# MCU.net
KiCad netlist of a schematic drawn in Altium Designer
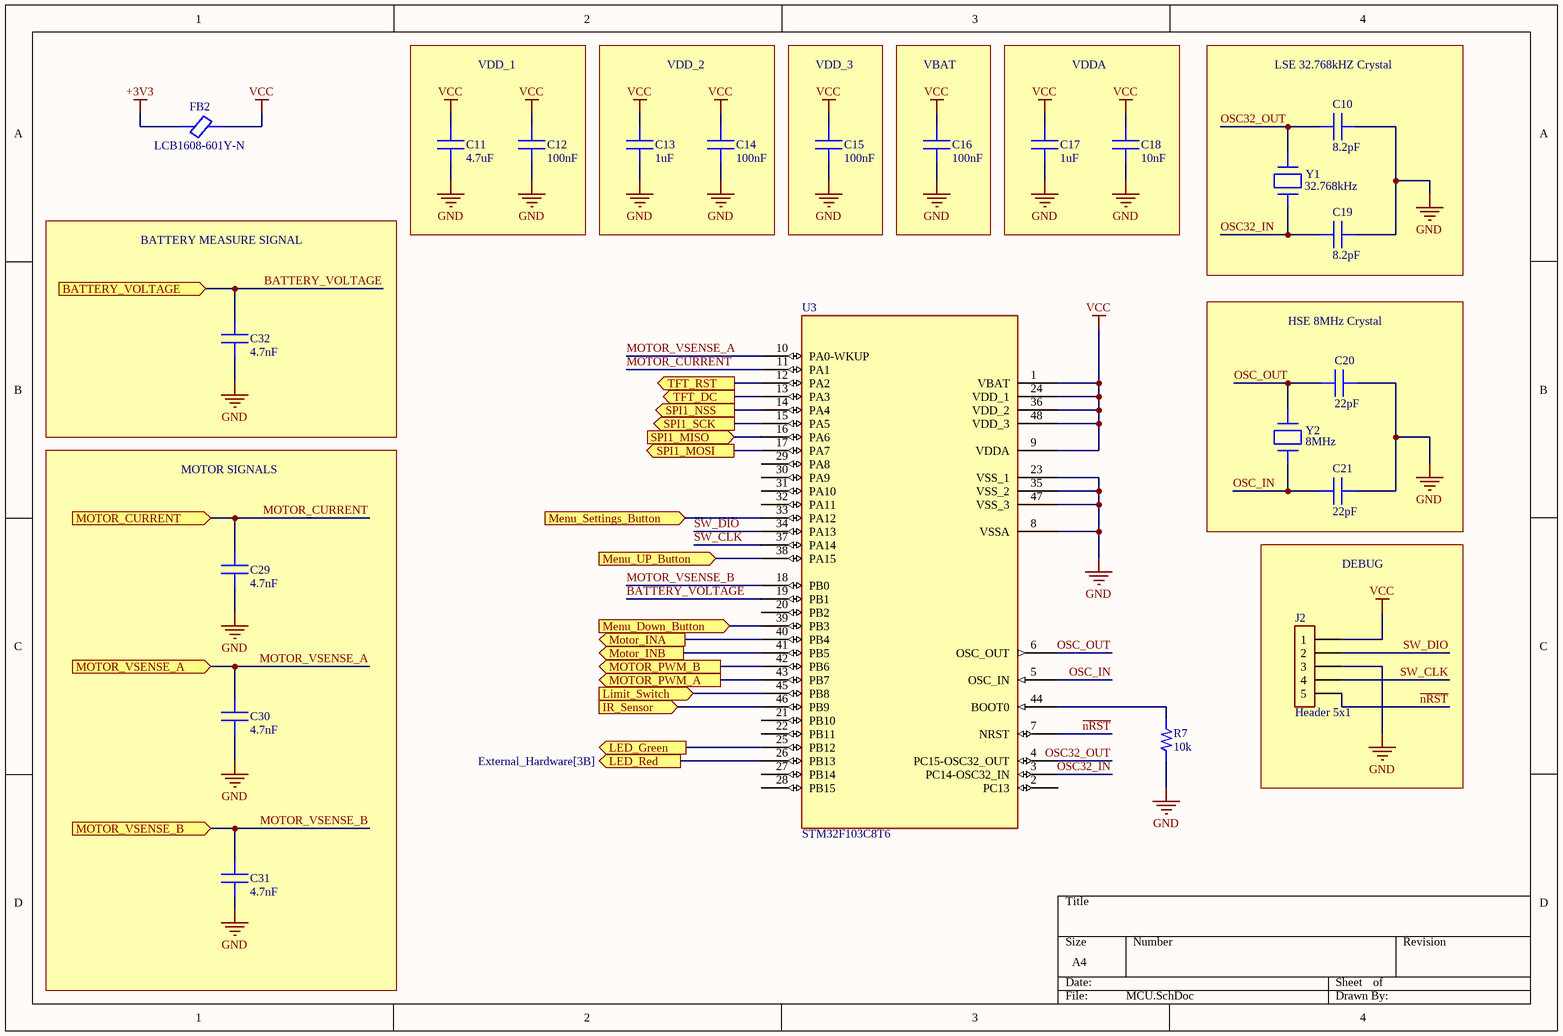
[diagram p0: MCU.SchDoc]

(export (version "E")
  (design (tool "Eeschema 10.0.6"))
  (components
    (comp (ref "C10")
      (value "8.2pF")
      (footprint "CAPC2012X145N 0805")
      (description "MLCC (2012) 0805 8.2pF 50VDC ±0.5pF C0G (NP0)")
      (fields (field (name "TOLERANCE") "±0.5 pF") (field (name "MANUFACTURER") "YAGEO"))
      (libsource (lib "Chicken_Coop_Door_Main_Board_V3") (part "CAP 0805 8.2pF CC0805DRNPO9BN8R2"))
    )
    (comp (ref "C11")
      (value "4.7uF")
      (footprint "CAPC2012X145N 0805")
      (description "MLCC (2012) 0805 4.7uF 16VDC ±10% X7R AUTOMOTIVE")
      (fields (field (name "TOLERANCE") "±10 %") (field (name "MANUFACTURER") "SAMSUNG"))
      (libsource (lib "Chicken_Coop_Door_Main_Board_V3") (part "CAP 0805 4.7uF CL21B475KOQVPNE"))
    )
    (comp (ref "C12")
      (value "100nF")
      (footprint "CAPC 0603 1608X90N")
      (description "MLCC (1608) 0603 100nF 25VDC ±10% X7R")
      (fields (field (name "TOLERANCE") "±10%") (field (name "MANUFACTURER") "YAGEO"))
      (libsource (lib "Chicken_Coop_Door_Main_Board_V3") (part "CAP 0603 100nF CC0603KPX7R8BB104"))
    )
    (comp (ref "C13")
      (value "1uF")
      (footprint "CAPC 0603 1608X90N")
      (description "MLCC (1608) 0603 1uF 16VDC ±10% X5R")
      (fields (field (name "TOLERANCE") "±10%") (field (name "MANUFACTURER") "KEMET"))
      (libsource (lib "Chicken_Coop_Door_Main_Board_V3") (part "CAP 0603 1uF C0603C105K4PACTU"))
    )
    (comp (ref "C14")
      (value "100nF")
      (footprint "CAPC 0603 1608X90N")
      (description "MLCC (1608) 0603 100nF 25VDC ±10% X7R")
      (fields (field (name "TOLERANCE") "±10%") (field (name "MANUFACTURER") "YAGEO"))
      (libsource (lib "Chicken_Coop_Door_Main_Board_V3") (part "CAP 0603 100nF CC0603KPX7R8BB104"))
    )
    (comp (ref "C15")
      (value "100nF")
      (footprint "CAPC 0603 1608X90N")
      (description "MLCC (1608) 0603 100nF 25VDC ±10% X7R")
      (fields (field (name "TOLERANCE") "±10%") (field (name "MANUFACTURER") "YAGEO"))
      (libsource (lib "Chicken_Coop_Door_Main_Board_V3") (part "CAP 0603 100nF CC0603KPX7R8BB104"))
    )
    (comp (ref "C16")
      (value "100nF")
      (footprint "CAPC 0603 1608X90N")
      (description "MLCC (1608) 0603 100nF 25VDC ±10% X7R")
      (fields (field (name "TOLERANCE") "±10%") (field (name "MANUFACTURER") "YAGEO"))
      (libsource (lib "Chicken_Coop_Door_Main_Board_V3") (part "CAP 0603 100nF CC0603KPX7R8BB104"))
    )
    (comp (ref "C17")
      (value "1uF")
      (footprint "CAPC 0603 1608X90N")
      (description "MLCC (1608) 0603 1uF 16VDC ±10% X5R")
      (fields (field (name "TOLERANCE") "±10%") (field (name "MANUFACTURER") "KEMET"))
      (libsource (lib "Chicken_Coop_Door_Main_Board_V3") (part "CAP 0603 1uF C0603C105K4PACTU"))
    )
    (comp (ref "C18")
      (value "10nF")
      (footprint "CAPC 0603 1608X90N")
      (description "MLCC (1608) 0603 10nF 25VDC ±10% X7R")
      (fields (field (name "TOLERANCE") "±10%") (field (name "MANUFACTURER") "SAMSUNG"))
      (libsource (lib "Chicken_Coop_Door_Main_Board_V3") (part "CAP 0603 10nF CL10B103KA8NNNC"))
    )
    (comp (ref "C19")
      (value "8.2pF")
      (footprint "CAPC2012X145N 0805")
      (description "MLCC (2012) 0805 8.2pF 50VDC ±0.5pF C0G (NP0)")
      (fields (field (name "TOLERANCE") "±0.5 pF") (field (name "MANUFACTURER") "YAGEO"))
      (libsource (lib "Chicken_Coop_Door_Main_Board_V3") (part "CAP 0805 8.2pF CC0805DRNPO9BN8R2"))
    )
    (comp (ref "C20")
      (value "22pF")
      (footprint "CAPC 0603 1608X90N")
      (description "MLCC (1608) 0603 22pF 50VDC ±5% C0G (NP0)")
      (fields (field (name "TOLERANCE") "±5 %") (field (name "MANUFACTURER") "YAGEO"))
      (libsource (lib "Chicken_Coop_Door_Main_Board_V3") (part "CAP 0603 22pF CC0603JRNPO9BN220"))
    )
    (comp (ref "C21")
      (value "22pF")
      (footprint "CAPC 0603 1608X90N")
      (description "MLCC (1608) 0603 22pF 50VDC ±5% C0G (NP0)")
      (fields (field (name "TOLERANCE") "±5 %") (field (name "MANUFACTURER") "YAGEO"))
      (libsource (lib "Chicken_Coop_Door_Main_Board_V3") (part "CAP 0603 22pF CC0603JRNPO9BN220"))
    )
    (comp (ref "C29")
      (value "4.7nF")
      (footprint "CAPC1608X90N 0603")
      (description "MLCC (1608) 0603 4.7nF 50VDC ±10% X7R")
      (fields (field (name "TOLERANCE") "±10 %") (field (name "MANUFACTURER") "SAMSUNG"))
      (libsource (lib "Chicken_Coop_Door_Main_Board_V3") (part "CAP 0603 4.7nF CL10B472KB8NNNC"))
    )
    (comp (ref "C30")
      (value "4.7nF")
      (footprint "CAPC1608X90N 0603")
      (description "MLCC (1608) 0603 4.7nF 50VDC ±10% X7R")
      (fields (field (name "TOLERANCE") "±10 %") (field (name "MANUFACTURER") "SAMSUNG"))
      (libsource (lib "Chicken_Coop_Door_Main_Board_V3") (part "CAP 0603 4.7nF CL10B472KB8NNNC"))
    )
    (comp (ref "C31")
      (value "4.7nF")
      (footprint "CAPC1608X90N 0603")
      (description "MLCC (1608) 0603 4.7nF 50VDC ±10% X7R")
      (fields (field (name "TOLERANCE") "±10 %") (field (name "MANUFACTURER") "SAMSUNG"))
      (libsource (lib "Chicken_Coop_Door_Main_Board_V3") (part "CAP 0603 4.7nF CL10B472KB8NNNC"))
    )
    (comp (ref "C32")
      (value "4.7nF")
      (footprint "CAPC1608X90N 0603")
      (description "MLCC (1608) 0603 4.7nF 50VDC ±10% X7R")
      (fields (field (name "TOLERANCE") "±10 %") (field (name "MANUFACTURER") "SAMSUNG"))
      (libsource (lib "Chicken_Coop_Door_Main_Board_V3") (part "CAP 0603 4.7nF CL10B472KB8NNNC"))
    )
    (comp (ref "FB2")
      (value "LCB1608-601Y-N")
      (footprint "MPZ1608S601ATA00 0603 1608X95N")
      (description "600 Ohms @ 100 MHz 1 Power Line Ferrite Bead 0603 (1608 Metric) 1A 200mOhm")
      (fields (field (name "TOLERANCE") "±25 %") (field (name "MANUFACTURER") "CORE MASTER"))
      (libsource (lib "Chicken_Coop_Door_Main_Board_V3") (part "Ferrite Bead LCB1608-601Y-N"))
    )
    (comp (ref "J2")
      (value "Header 5x1")
      (footprint "Header 5x1 FEMALE Header")
      (description "FEMALE HEADER 5PIN(1x5) 2.54mm THT V/T BAG")
      (fields (field (name "MANUFACTURER") "KLS ELECTRONIC"))
      (libsource (lib "Chicken_Coop_Door_Main_Board_V3") (part "Header 5x1 Female Header"))
    )
    (comp (ref "R7")
      (value "10k")
      (footprint "RES 0603 ROYALOHM")
      (description "RES.(1608) 0603 10K Ohms 5% 1/10W-S 100PPM")
      (fields (field (name "TOLERANCE") "±5 %") (field (name "MANUFACTURER") "ROYALOHM"))
      (libsource (lib "Chicken_Coop_Door_Main_Board_V3") (part "RES 0603 10k 0603SAJ0103T5E"))
    )
    (comp (ref "U3")
      (value "STM32F103C8T6")
      (footprint "LQFP48_STM")
      (fields (field (name "COPYRIGHT") "Copyright (C) 2025 Ultra Librarian. All rights reserved."))
      (libsource (lib "Chicken_Coop_Door_Main_Board") (part "STM32F103C8T6"))
    )
    (comp (ref "Y1")
      (value "32.768kHz")
      (footprint "XTAL_ABS07-120-32.768KHZ-T")
      (description "CRYSTAL 32.768kHz 6pF SMD")
      (fields (field (name "MANUFACTURER") "Abracon LLC"))
      (libsource (lib "Chicken_Coop_Door_Main_Board_V3") (part "CRYSTAL 32.768kHz ABS07-120-32.768KHZ-T"))
    )
    (comp (ref "Y2")
      (value "8MHz")
      (footprint "XTAL_J49SMH-A-G-G-K-8M0_JAU")
      (description "CRYSTAL 8MHz HC49SMT 16pF SMD TR RALTRON")
      (fields (field (name "MANUFACTURER") "RALTRON"))
      (libsource (lib "Chicken_Coop_Door_Main_Board_V3") (part "CRYSTAL 8MHz AS-8.000-16-SMD-TR"))
    )
  )
  (nets
    (net (code "1") (name "+3V3") (class "Default")
      (node (ref "FB2") (pin "1") (pinfunction "1_1") (pintype "passive"))
    )
    (net (code "2") (name "/BATTERY_VOLTAGE") (class "Default")
      (node (ref "C32") (pin "2") (pinfunction "2_2") (pintype "passive"))
      (node (ref "U3") (pin "19") (pinfunction "PB1_19") (pintype "bidirectional"))
    )
    (net (code "3") (name "/IR_Sensor") (class "Default")
      (node (ref "U3") (pin "46") (pinfunction "PB9_46") (pintype "bidirectional"))
    )
    (net (code "4") (name "/LED_Green") (class "Default")
      (node (ref "U3") (pin "25") (pinfunction "PB12_25") (pintype "bidirectional"))
    )
    (net (code "5") (name "/LED_Red") (class "Default")
      (node (ref "U3") (pin "26") (pinfunction "PB13_26") (pintype "bidirectional"))
    )
    (net (code "6") (name "/Limit_Switch") (class "Default")
      (node (ref "U3") (pin "45") (pinfunction "PB8_45") (pintype "bidirectional"))
    )
    (net (code "7") (name "/MOTOR_CURRENT") (class "Default")
      (node (ref "C29") (pin "2") (pinfunction "2_2") (pintype "passive"))
      (node (ref "U3") (pin "11") (pinfunction "PA1_11") (pintype "bidirectional"))
    )
    (net (code "8") (name "/MOTOR_PWM_A") (class "Default")
      (node (ref "U3") (pin "43") (pinfunction "PB7_43") (pintype "bidirectional"))
    )
    (net (code "9") (name "/MOTOR_PWM_B") (class "Default")
      (node (ref "U3") (pin "42") (pinfunction "PB6_42") (pintype "bidirectional"))
    )
    (net (code "10") (name "/MOTOR_VSENSE_A") (class "Default")
      (node (ref "C30") (pin "2") (pinfunction "2_2") (pintype "passive"))
      (node (ref "U3") (pin "10") (pinfunction "PA0-WKUP_10") (pintype "bidirectional"))
    )
    (net (code "11") (name "/MOTOR_VSENSE_B") (class "Default")
      (node (ref "C31") (pin "2") (pinfunction "2_2") (pintype "passive"))
      (node (ref "U3") (pin "18") (pinfunction "PB0_18") (pintype "bidirectional"))
    )
    (net (code "12") (name "/Menu_Down_Button") (class "Default")
      (node (ref "U3") (pin "39") (pinfunction "PB3_39") (pintype "bidirectional"))
    )
    (net (code "13") (name "/Menu_Settings_Button") (class "Default")
      (node (ref "U3") (pin "33") (pinfunction "PA12_33") (pintype "bidirectional"))
    )
    (net (code "14") (name "/Menu_UP_Button") (class "Default")
      (node (ref "U3") (pin "38") (pinfunction "PA15_38") (pintype "bidirectional"))
    )
    (net (code "15") (name "/Motor_INA") (class "Default")
      (node (ref "U3") (pin "40") (pinfunction "PB4_40") (pintype "bidirectional"))
    )
    (net (code "16") (name "/Motor_INB") (class "Default")
      (node (ref "U3") (pin "41") (pinfunction "PB5_41") (pintype "bidirectional"))
    )
    (net (code "17") (name "/OSC32_IN") (class "Default")
      (node (ref "C19") (pin "1") (pinfunction "1_1") (pintype "passive"))
      (node (ref "U3") (pin "3") (pinfunction "PC14-OSC32_IN_3") (pintype "bidirectional"))
      (node (ref "Y1") (pin "1") (pinfunction "1_1") (pintype "passive"))
    )
    (net (code "18") (name "/OSC32_OUT") (class "Default")
      (node (ref "C10") (pin "1") (pinfunction "1_1") (pintype "passive"))
      (node (ref "U3") (pin "4") (pinfunction "PC15-OSC32_OUT_4") (pintype "bidirectional"))
      (node (ref "Y1") (pin "2") (pinfunction "2_2") (pintype "passive"))
    )
    (net (code "19") (name "/OSC_IN") (class "Default")
      (node (ref "C21") (pin "1") (pinfunction "1_1") (pintype "passive"))
      (node (ref "U3") (pin "5") (pinfunction "OSC_IN_5") (pintype "input"))
      (node (ref "Y2") (pin "1") (pinfunction "1_1") (pintype "passive"))
    )
    (net (code "20") (name "/OSC_OUT") (class "Default")
      (node (ref "C20") (pin "1") (pinfunction "1_1") (pintype "passive"))
      (node (ref "U3") (pin "6") (pinfunction "OSC_OUT_6") (pintype "output"))
      (node (ref "Y2") (pin "2") (pinfunction "2_2") (pintype "passive"))
    )
    (net (code "21") (name "/SPI1_MISO") (class "Default")
      (node (ref "U3") (pin "16") (pinfunction "PA6_16") (pintype "bidirectional"))
    )
    (net (code "22") (name "/SPI1_MOSI") (class "Default")
      (node (ref "U3") (pin "17") (pinfunction "PA7_17") (pintype "bidirectional"))
    )
    (net (code "23") (name "/SPI1_NSS") (class "Default")
      (node (ref "U3") (pin "14") (pinfunction "PA4_14") (pintype "bidirectional"))
    )
    (net (code "24") (name "/SPI1_SCK") (class "Default")
      (node (ref "U3") (pin "15") (pinfunction "PA5_15") (pintype "bidirectional"))
    )
    (net (code "25") (name "/SW_CLK") (class "Default")
      (node (ref "J2") (pin "4") (pinfunction "4_4") (pintype "passive"))
      (node (ref "U3") (pin "37") (pinfunction "PA14_37") (pintype "bidirectional"))
    )
    (net (code "26") (name "/SW_DIO") (class "Default")
      (node (ref "J2") (pin "2") (pinfunction "2_2") (pintype "passive"))
      (node (ref "U3") (pin "34") (pinfunction "PA13_34") (pintype "bidirectional"))
    )
    (net (code "27") (name "/TFT_DC") (class "Default")
      (node (ref "U3") (pin "13") (pinfunction "PA3_13") (pintype "bidirectional"))
    )
    (net (code "28") (name "/TFT_RST") (class "Default")
      (node (ref "U3") (pin "12") (pinfunction "PA2_12") (pintype "bidirectional"))
    )
    (net (code "29") (name "/~{nRST}") (class "Default")
      (node (ref "J2") (pin "5") (pinfunction "5_5") (pintype "passive"))
      (node (ref "U3") (pin "7") (pinfunction "NRST_7") (pintype "bidirectional"))
    )
    (net (code "30") (name "GND") (class "Default")
      (node (ref "C10") (pin "2") (pinfunction "2_2") (pintype "passive"))
      (node (ref "C11") (pin "1") (pinfunction "1_1") (pintype "passive"))
      (node (ref "C12") (pin "1") (pinfunction "1_1") (pintype "passive"))
      (node (ref "C13") (pin "1") (pinfunction "1_1") (pintype "passive"))
      (node (ref "C14") (pin "1") (pinfunction "1_1") (pintype "passive"))
      (node (ref "C15") (pin "1") (pinfunction "1_1") (pintype "passive"))
      (node (ref "C16") (pin "1") (pinfunction "1_1") (pintype "passive"))
      (node (ref "C17") (pin "1") (pinfunction "1_1") (pintype "passive"))
      (node (ref "C18") (pin "1") (pinfunction "1_1") (pintype "passive"))
      (node (ref "C19") (pin "2") (pinfunction "2_2") (pintype "passive"))
      (node (ref "C20") (pin "2") (pinfunction "2_2") (pintype "passive"))
      (node (ref "C21") (pin "2") (pinfunction "2_2") (pintype "passive"))
      (node (ref "C29") (pin "1") (pinfunction "1_1") (pintype "passive"))
      (node (ref "C30") (pin "1") (pinfunction "1_1") (pintype "passive"))
      (node (ref "C31") (pin "1") (pinfunction "1_1") (pintype "passive"))
      (node (ref "C32") (pin "1") (pinfunction "1_1") (pintype "passive"))
      (node (ref "J2") (pin "3") (pinfunction "3_3") (pintype "passive"))
      (node (ref "R7") (pin "1") (pinfunction "1_1") (pintype "passive"))
      (node (ref "U3") (pin "23") (pinfunction "VSS_1_23") (pintype "power_in"))
      (node (ref "U3") (pin "35") (pinfunction "VSS_2_35") (pintype "power_in"))
      (node (ref "U3") (pin "47") (pinfunction "VSS_3_47") (pintype "power_in"))
      (node (ref "U3") (pin "8") (pinfunction "VSSA_8") (pintype "power_in"))
    )
    (net (code "31") (name "Net-(U3-BOOT0)") (class "Default")
      (node (ref "R7") (pin "2") (pinfunction "2_2") (pintype "passive"))
      (node (ref "U3") (pin "44") (pinfunction "BOOT0_44") (pintype "input"))
    )
    (net (code "32") (name "VCC") (class "Default")
      (node (ref "C11") (pin "2") (pinfunction "2_2") (pintype "passive"))
      (node (ref "C12") (pin "2") (pinfunction "2_2") (pintype "passive"))
      (node (ref "C13") (pin "2") (pinfunction "2_2") (pintype "passive"))
      (node (ref "C14") (pin "2") (pinfunction "2_2") (pintype "passive"))
      (node (ref "C15") (pin "2") (pinfunction "2_2") (pintype "passive"))
      (node (ref "C16") (pin "2") (pinfunction "2_2") (pintype "passive"))
      (node (ref "C17") (pin "2") (pinfunction "2_2") (pintype "passive"))
      (node (ref "C18") (pin "2") (pinfunction "2_2") (pintype "passive"))
      (node (ref "FB2") (pin "2") (pinfunction "2_2") (pintype "passive"))
      (node (ref "J2") (pin "1") (pinfunction "1_1") (pintype "passive"))
      (node (ref "U3") (pin "1") (pinfunction "VBAT_1") (pintype "power_in"))
      (node (ref "U3") (pin "24") (pinfunction "VDD_1_24") (pintype "power_in"))
      (node (ref "U3") (pin "36") (pinfunction "VDD_2_36") (pintype "power_in"))
      (node (ref "U3") (pin "48") (pinfunction "VDD_3_48") (pintype "power_in"))
      (node (ref "U3") (pin "9") (pinfunction "VDDA_9") (pintype "power_in"))
    )
    (net (code "33") (name "unconnected-(U3-PA8-Pad29)") (class "Default")
      (node (ref "U3") (pin "29") (pinfunction "PA8_29") (pintype "bidirectional"))
    )
    (net (code "34") (name "unconnected-(U3-PA9-Pad30)") (class "Default")
      (node (ref "U3") (pin "30") (pinfunction "PA9_30") (pintype "bidirectional"))
    )
    (net (code "35") (name "unconnected-(U3-PA10-Pad31)") (class "Default")
      (node (ref "U3") (pin "31") (pinfunction "PA10_31") (pintype "bidirectional"))
    )
    (net (code "36") (name "unconnected-(U3-PA11-Pad32)") (class "Default")
      (node (ref "U3") (pin "32") (pinfunction "PA11_32") (pintype "bidirectional"))
    )
    (net (code "37") (name "unconnected-(U3-PB2-Pad20)") (class "Default")
      (node (ref "U3") (pin "20") (pinfunction "PB2_20") (pintype "bidirectional"))
    )
    (net (code "38") (name "unconnected-(U3-PB10-Pad21)") (class "Default")
      (node (ref "U3") (pin "21") (pinfunction "PB10_21") (pintype "bidirectional"))
    )
    (net (code "39") (name "unconnected-(U3-PB11-Pad22)") (class "Default")
      (node (ref "U3") (pin "22") (pinfunction "PB11_22") (pintype "bidirectional"))
    )
    (net (code "40") (name "unconnected-(U3-PB14-Pad27)") (class "Default")
      (node (ref "U3") (pin "27") (pinfunction "PB14_27") (pintype "bidirectional"))
    )
    (net (code "41") (name "unconnected-(U3-PB15-Pad28)") (class "Default")
      (node (ref "U3") (pin "28") (pinfunction "PB15_28") (pintype "bidirectional"))
    )
    (net (code "42") (name "unconnected-(U3-PC13-Pad2)") (class "Default")
      (node (ref "U3") (pin "2") (pinfunction "PC13_2") (pintype "bidirectional"))
    )
  )
)
